# Nixie_power_supply_v1_0_2.net
KiCad netlist of a schematic drawn in EAGLE
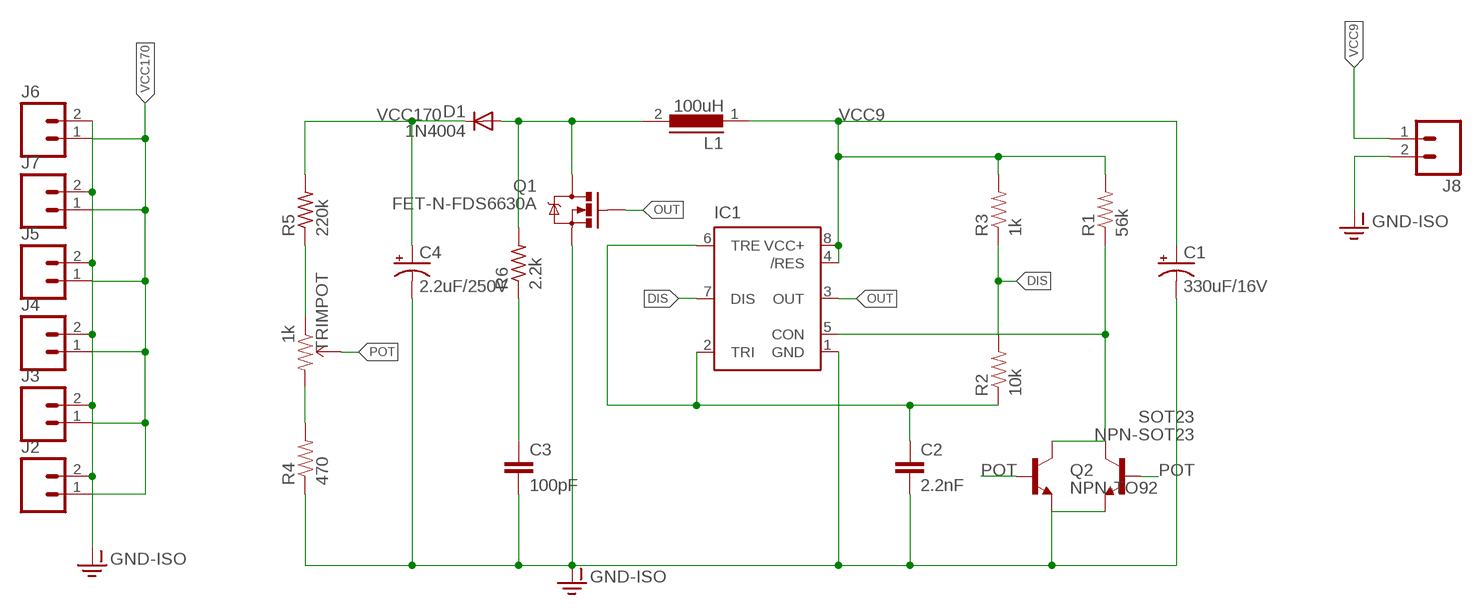
[diagram p0: schematic, sheet 1]

(export (version "E")
  (design (tool "Eeschema 10.0.6"))
  (components
    (comp (ref "C1")
      (value "330uF/16V")
      (footprint "eagle-import:E3,5-8")
      (libsource (lib "eagle-import") (part "CPOL-USE3.5-8"))
    )
    (comp (ref "C2")
      (value "2.2nF")
      (footprint "eagle-import:0805")
      (libsource (lib "eagle-import") (part "CAP0805"))
    )
    (comp (ref "C3")
      (value "100pF")
      (footprint "eagle-import:C1005")
      (libsource (lib "eagle-import") (part "C-EUC1005"))
    )
    (comp (ref "C4")
      (value "2.2uF/250V")
      (footprint "eagle-import:CPOL-RADIAL-100UF-25V")
      (libsource (lib "eagle-import") (part "CAP_POLPTH1"))
    )
    (comp (ref "D1")
      (value "1N4004")
      (footprint "eagle-import:DO41-10")
      (libsource (lib "eagle-import") (part "1N4004"))
    )
    (comp (ref "IC1")
      (value "NE555D")
      (footprint "eagle-import:SO08")
      (libsource (lib "eagle-import") (part "NE555D"))
    )
    (comp (ref "J2")
      (value "M02LOCK")
      (footprint "eagle-import:1X02_LOCK")
      (libsource (lib "eagle-import") (part "M02LOCK"))
    )
    (comp (ref "J3")
      (value "M02LOCK")
      (footprint "eagle-import:1X02_LOCK")
      (libsource (lib "eagle-import") (part "M02LOCK"))
    )
    (comp (ref "J4")
      (value "M02LOCK")
      (footprint "eagle-import:1X02_LOCK")
      (libsource (lib "eagle-import") (part "M02LOCK"))
    )
    (comp (ref "J5")
      (value "M02LOCK")
      (footprint "eagle-import:1X02_LOCK")
      (libsource (lib "eagle-import") (part "M02LOCK"))
    )
    (comp (ref "J6")
      (value "M02LOCK")
      (footprint "eagle-import:1X02_LOCK")
      (libsource (lib "eagle-import") (part "M02LOCK"))
    )
    (comp (ref "J7")
      (value "M02LOCK")
      (footprint "eagle-import:1X02_LOCK")
      (libsource (lib "eagle-import") (part "M02LOCK"))
    )
    (comp (ref "J8")
      (value "M02LOCK")
      (footprint "eagle-import:1X02_LOCK")
      (libsource (lib "eagle-import") (part "M02LOCK"))
    )
    (comp (ref "L1")
      (value "100uH")
      (footprint "eagle-import:DR74")
      (libsource (lib "eagle-import") (part "DR74"))
    )
    (comp (ref "Q1")
      (value "FET-N-FDS6630A")
      (footprint "eagle-import:SO08")
      (libsource (lib "eagle-import") (part "MOSFET-NCHANNELFDS6630A"))
    )
    (comp (ref "Q2")
      (value "NPN-TO92")
      (footprint "eagle-import:TO-92-AMMO")
      (libsource (lib "eagle-import") (part "TRANSISTOR_NPNBC547"))
    )
    (comp (ref "R1")
      (value "56k")
      (footprint "eagle-import:0805")
      (libsource (lib "eagle-import") (part "RESISTOR0805-RES"))
    )
    (comp (ref "R2")
      (value "10k")
      (footprint "eagle-import:0805")
      (libsource (lib "eagle-import") (part "RESISTOR0805-RES"))
    )
    (comp (ref "R3")
      (value "1k")
      (footprint "eagle-import:0805")
      (libsource (lib "eagle-import") (part "RESISTOR0805-RES"))
    )
    (comp (ref "R4")
      (value "470")
      (footprint "eagle-import:0805")
      (libsource (lib "eagle-import") (part "RESISTOR0805-RES"))
    )
    (comp (ref "R5")
      (value "220k")
      (footprint "eagle-import:R1206")
      (libsource (lib "eagle-import") (part "R-US_R1206"))
    )
    (comp (ref "R6")
      (value "2.2k")
      (footprint "eagle-import:R1206")
      (libsource (lib "eagle-import") (part "R-US_R1206"))
    )
    (comp (ref "SOT23")
      (value "NPN-SOT23")
      (footprint "eagle-import:SOT23-BEC")
      (libsource (lib "eagle-import") (part "-NPN-SOT23-BECBC817-16"))
    )
    (comp (ref "TRIMPOT")
      (value "1k")
      (footprint "eagle-import:TRIMPOT_TC33")
      (libsource (lib "eagle-import") (part "TRIMPOT-2"))
    )
  )
  (nets
    (net (code "1") (name "DIS") (class "Default")
      (node (ref "IC1") (pin "7") (pinfunction "DIS_7") (pintype "input"))
      (node (ref "R2") (pin "2") (pinfunction "2_2") (pintype "passive"))
      (node (ref "R3") (pin "1") (pinfunction "1_1") (pintype "passive"))
    )
    (net (code "2") (name "GND-ISO") (class "Default")
      (node (ref "C1") (pin "-") (pinfunction "-_-") (pintype "passive"))
      (node (ref "C2") (pin "2") (pinfunction "2_2") (pintype "passive"))
      (node (ref "C3") (pin "2") (pinfunction "2_2") (pintype "passive"))
      (node (ref "C4") (pin "2") (pinfunction "-_2") (pintype "passive"))
      (node (ref "IC1") (pin "1") (pinfunction "GND_1") (pintype "power_in"))
      (node (ref "J2") (pin "2") (pinfunction "2_2") (pintype "passive"))
      (node (ref "J3") (pin "2") (pinfunction "2_2") (pintype "passive"))
      (node (ref "J4") (pin "2") (pinfunction "2_2") (pintype "passive"))
      (node (ref "J5") (pin "2") (pinfunction "2_2") (pintype "passive"))
      (node (ref "J6") (pin "2") (pinfunction "2_2") (pintype "passive"))
      (node (ref "J7") (pin "2") (pinfunction "2_2") (pintype "passive"))
      (node (ref "J8") (pin "2") (pinfunction "2_2") (pintype "passive"))
      (node (ref "Q1") (pin "1") (pinfunction "S_1") (pintype "passive"))
      (node (ref "Q1") (pin "2") (pinfunction "S_2") (pintype "passive"))
      (node (ref "Q1") (pin "3") (pinfunction "S_3") (pintype "passive"))
      (node (ref "Q2") (pin "3") (pinfunction "E_3") (pintype "passive"))
      (node (ref "R4") (pin "1") (pinfunction "1_1") (pintype "passive"))
      (node (ref "SOT23") (pin "E") (pinfunction "E_E") (pintype "passive"))
    )
    (net (code "3") (name "Net-(C3-Pad1)") (class "Default")
      (node (ref "C3") (pin "1") (pinfunction "1_1") (pintype "passive"))
      (node (ref "R6") (pin "1") (pinfunction "1_1") (pintype "passive"))
    )
    (net (code "4") (name "Net-(D1-PadA)") (class "Default")
      (node (ref "D1") (pin "A") (pinfunction "A_A") (pintype "passive"))
      (node (ref "L1") (pin "2") (pinfunction "2_2") (pintype "passive"))
      (node (ref "Q1") (pin "5") (pinfunction "D_5") (pintype "passive"))
      (node (ref "Q1") (pin "6") (pinfunction "D_6") (pintype "passive"))
      (node (ref "Q1") (pin "7") (pinfunction "D_7") (pintype "passive"))
      (node (ref "Q1") (pin "8") (pinfunction "D_8") (pintype "passive"))
      (node (ref "R6") (pin "2") (pinfunction "2_2") (pintype "passive"))
    )
    (net (code "5") (name "Net-(IC1-CON)") (class "Default")
      (node (ref "IC1") (pin "5") (pinfunction "CON_5") (pintype "input"))
      (node (ref "Q2") (pin "1") (pinfunction "C_1") (pintype "passive"))
      (node (ref "R1") (pin "1") (pinfunction "1_1") (pintype "passive"))
      (node (ref "SOT23") (pin "C") (pinfunction "C_C") (pintype "passive"))
    )
    (net (code "6") (name "Net-(IC1-TRE)") (class "Default")
      (node (ref "C2") (pin "1") (pinfunction "1_1") (pintype "passive"))
      (node (ref "IC1") (pin "2") (pinfunction "TRI_2") (pintype "input"))
      (node (ref "IC1") (pin "6") (pinfunction "TRE_6") (pintype "input"))
      (node (ref "R2") (pin "1") (pinfunction "1_1") (pintype "passive"))
    )
    (net (code "7") (name "Net-(TRIMPOT-CCW)") (class "Default")
      (node (ref "R5") (pin "1") (pinfunction "1_1") (pintype "passive"))
      (node (ref "TRIMPOT") (pin "1") (pinfunction "CCW_1") (pintype "passive"))
    )
    (net (code "8") (name "Net-(TRIMPOT-CW)") (class "Default")
      (node (ref "R4") (pin "2") (pinfunction "2_2") (pintype "passive"))
      (node (ref "TRIMPOT") (pin "3") (pinfunction "CW_3") (pintype "passive"))
    )
    (net (code "9") (name "OUT") (class "Default")
      (node (ref "IC1") (pin "3") (pinfunction "OUT_3") (pintype "output"))
      (node (ref "Q1") (pin "4") (pinfunction "G_4") (pintype "passive"))
    )
    (net (code "10") (name "POT") (class "Default")
      (node (ref "Q2") (pin "2") (pinfunction "B_2") (pintype "passive"))
      (node (ref "SOT23") (pin "B") (pinfunction "B_B") (pintype "passive"))
      (node (ref "TRIMPOT") (pin "2") (pinfunction "WIPER_2") (pintype "passive"))
    )
    (net (code "11") (name "VCC9") (class "Default")
      (node (ref "C1") (pin "+") (pinfunction "+_+") (pintype "passive"))
      (node (ref "IC1") (pin "4") (pinfunction "/RES_4") (pintype "input"))
      (node (ref "IC1") (pin "8") (pinfunction "VCC+_8") (pintype "power_in"))
      (node (ref "J8") (pin "1") (pinfunction "1_1") (pintype "passive"))
      (node (ref "L1") (pin "1") (pinfunction "1_1") (pintype "passive"))
      (node (ref "R1") (pin "2") (pinfunction "2_2") (pintype "passive"))
      (node (ref "R3") (pin "2") (pinfunction "2_2") (pintype "passive"))
    )
    (net (code "12") (name "VCC170") (class "Default")
      (node (ref "C4") (pin "1") (pinfunction "+_1") (pintype "passive"))
      (node (ref "D1") (pin "C") (pinfunction "C_C") (pintype "passive"))
      (node (ref "J2") (pin "1") (pinfunction "1_1") (pintype "passive"))
      (node (ref "J3") (pin "1") (pinfunction "1_1") (pintype "passive"))
      (node (ref "J4") (pin "1") (pinfunction "1_1") (pintype "passive"))
      (node (ref "J5") (pin "1") (pinfunction "1_1") (pintype "passive"))
      (node (ref "J6") (pin "1") (pinfunction "1_1") (pintype "passive"))
      (node (ref "J7") (pin "1") (pinfunction "1_1") (pintype "passive"))
      (node (ref "R5") (pin "2") (pinfunction "2_2") (pintype "passive"))
    )
  )
)
